# piboard.net
KiCad netlist of a schematic drawn in EAGLE
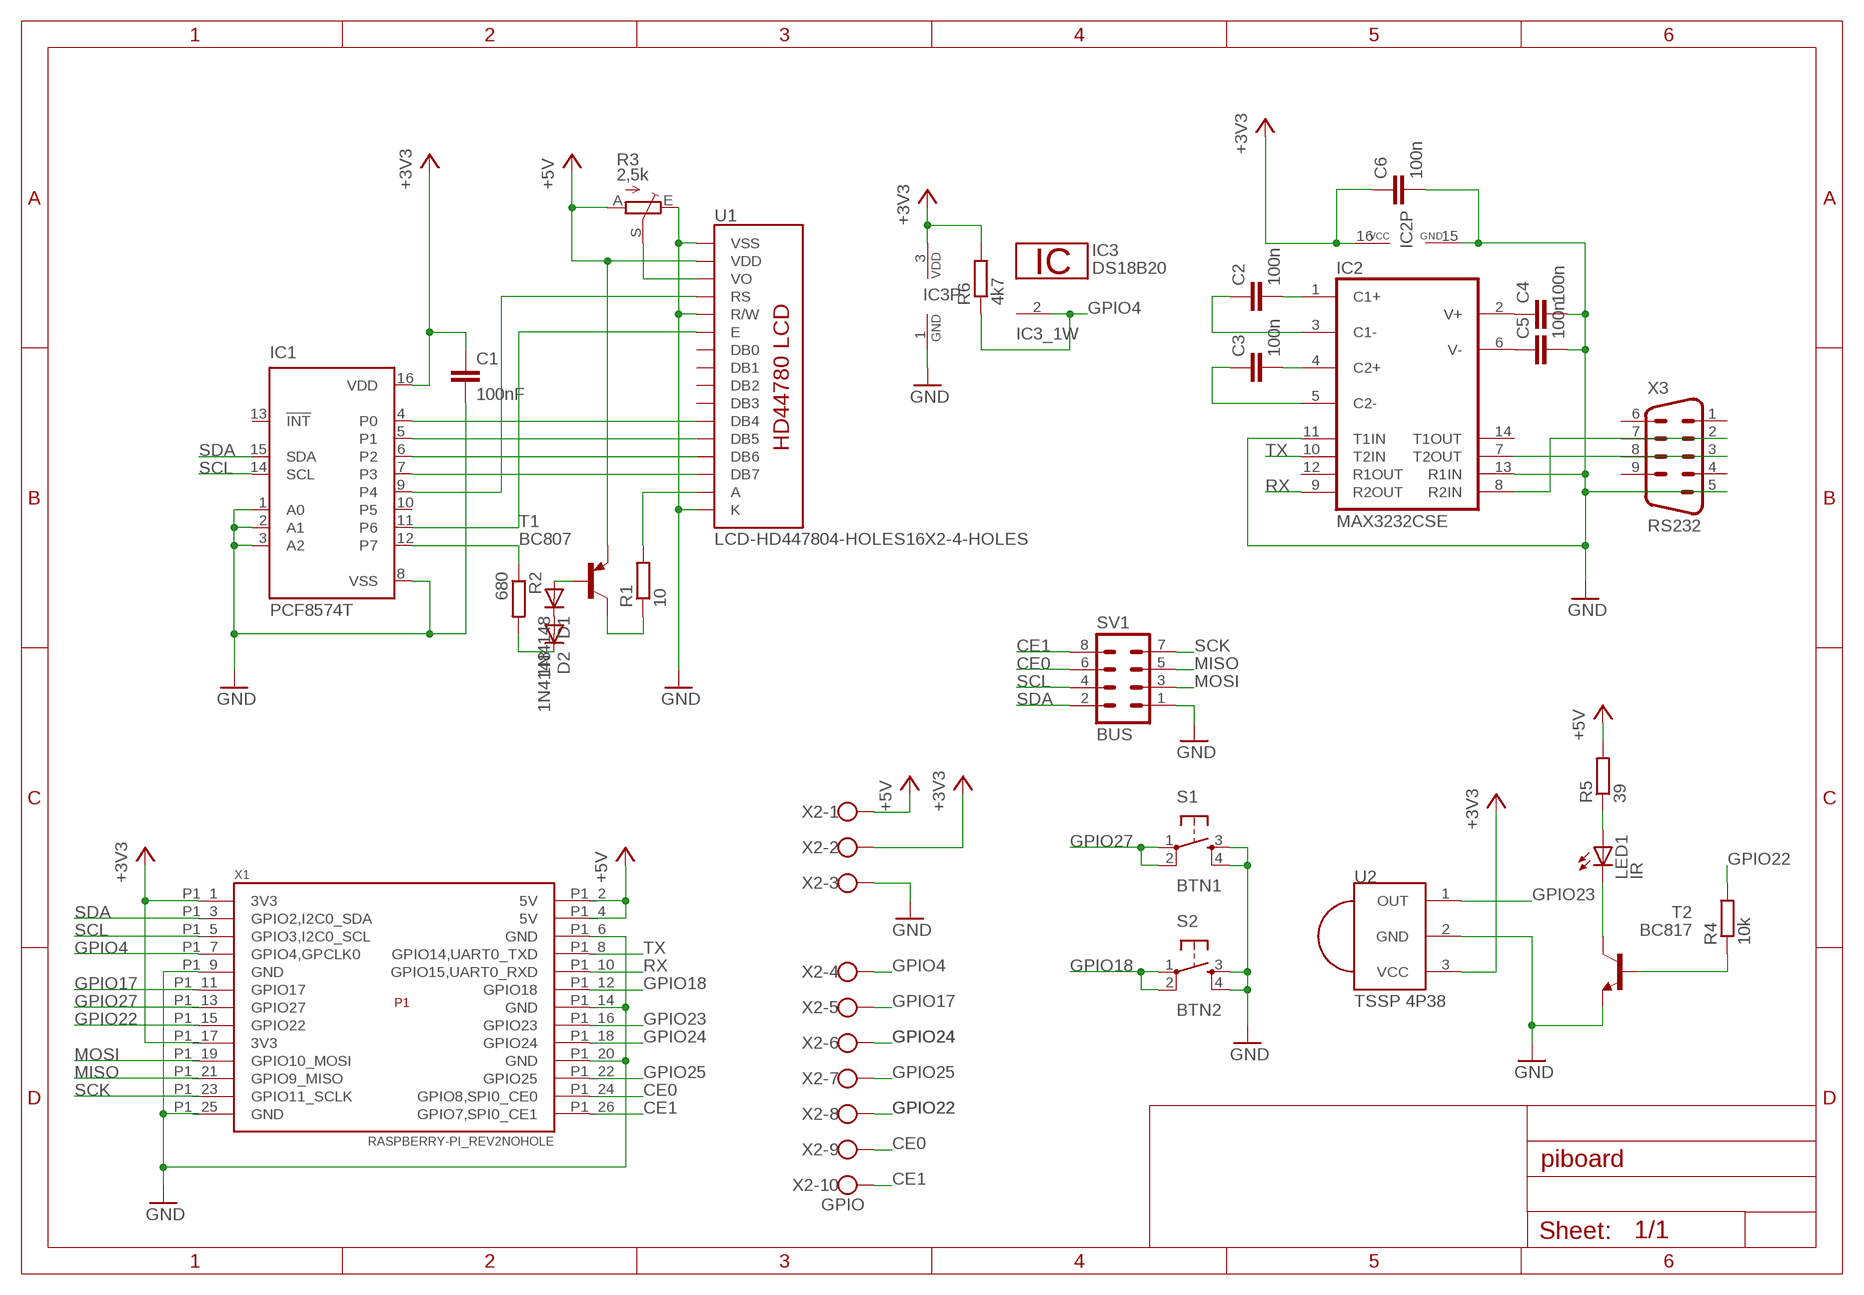
[diagram p0: schematic, sheet 1]

(export (version "E")
  (design (tool "Eeschema 10.0.6"))
  (components
    (comp (ref "C1")
      (value "100nF")
      (footprint "eagle-import:C0805")
      (libsource (lib "eagle-import") (part "C-EUC0805"))
    )
    (comp (ref "C2")
      (value "100n")
      (footprint "eagle-import:C0805")
      (libsource (lib "eagle-import") (part "C-EUC0805"))
    )
    (comp (ref "C3")
      (value "100n")
      (footprint "eagle-import:C0805")
      (libsource (lib "eagle-import") (part "C-EUC0805"))
    )
    (comp (ref "C4")
      (value "100n")
      (footprint "eagle-import:C0805")
      (libsource (lib "eagle-import") (part "C-EUC0805"))
    )
    (comp (ref "C5")
      (value "100n")
      (footprint "eagle-import:C0805")
      (libsource (lib "eagle-import") (part "C-EUC0805"))
    )
    (comp (ref "C6")
      (value "100n")
      (footprint "eagle-import:C0805")
      (libsource (lib "eagle-import") (part "C-EUC0805"))
    )
    (comp (ref "D1")
      (value "1N4148")
      (footprint "eagle-import:SOD80C")
      (libsource (lib "eagle-import") (part "DIODE-SOD80C"))
    )
    (comp (ref "D2")
      (value "1N4148")
      (footprint "eagle-import:SOD80C")
      (libsource (lib "eagle-import") (part "DIODE-SOD80C"))
    )
    (comp (ref "IC1")
      (value "PCF8574T")
      (footprint "eagle-import:SO16W")
      (fields (field (name "MPN") "PCF8574T/3,512"))
      (libsource (lib "eagle-import") (part "PCF8574T"))
    )
    (comp (ref "IC2")
      (value "MAX3232CSE")
      (footprint "eagle-import:SO16")
      (libsource (lib "eagle-import") (part "MAX3232SEC"))
    )
    (comp (ref "IC3")
      (value "DS18B20")
      (footprint "eagle-import:TO92-")
      (libsource (lib "eagle-import") (part "DS18B20"))
    )
    (comp (ref "LED1")
      (value "IR")
      (footprint "eagle-import:LED5MM")
      (libsource (lib "eagle-import") (part "LED5MM"))
    )
    (comp (ref "R1")
      (value "10")
      (footprint "eagle-import:R0805")
      (libsource (lib "eagle-import") (part "R-EU_R0805"))
    )
    (comp (ref "R2")
      (value "680")
      (footprint "eagle-import:R0805")
      (libsource (lib "eagle-import") (part "R-EU_R0805"))
    )
    (comp (ref "R3")
      (value "2,5k")
      (footprint "eagle-import:LI6")
      (libsource (lib "eagle-import") (part "TRIM_EU-2"))
    )
    (comp (ref "R4")
      (value "10k")
      (footprint "eagle-import:R0805")
      (libsource (lib "eagle-import") (part "R-EU_R0805"))
    )
    (comp (ref "R5")
      (value "39")
      (footprint "eagle-import:R0805")
      (libsource (lib "eagle-import") (part "R-EU_R0805"))
    )
    (comp (ref "R6")
      (value "4k7")
      (footprint "eagle-import:R0805")
      (libsource (lib "eagle-import") (part "R-EU_R0805"))
    )
    (comp (ref "S1")
      (value "BTN1")
      (footprint "eagle-import:TACTILE-PTH")
      (libsource (lib "eagle-import") (part "TAC_SWITCHPTH"))
    )
    (comp (ref "S2")
      (value "BTN2")
      (footprint "eagle-import:TACTILE-PTH")
      (libsource (lib "eagle-import") (part "TAC_SWITCHPTH"))
    )
    (comp (ref "SV1")
      (value "BUS")
      (footprint "eagle-import:MA04-2")
      (libsource (lib "eagle-import") (part "MA04-2"))
    )
    (comp (ref "T1")
      (value "BC807")
      (footprint "eagle-import:SOT23-BEC")
      (libsource (lib "eagle-import") (part "-PNP-SOT23-BECBC807-16"))
    )
    (comp (ref "T2")
      (value "BC817")
      (footprint "eagle-import:SOT23-BEC")
      (libsource (lib "eagle-import") (part "-NPN-SOT23-BECBC817-16"))
    )
    (comp (ref "U1")
      (value "LCD-HD447804-HOLES16X2-4-HOLES")
      (footprint "eagle-import:LCD-16X2-4HOLES")
      (libsource (lib "eagle-import") (part "LCD-HD4478016X2-4-HOLES4-HOLES"))
    )
    (comp (ref "U2")
      (value "TSSP 4P38")
      (footprint "eagle-import:PNA460XM")
      (libsource (lib "eagle-import") (part "adafruit-eagle610_PNA460XM"))
    )
    (comp (ref "X1")
      (value "RASPBERRY-PI_REV2NOHOLE")
      (footprint "eagle-import:RASPBERRY-PI_REV2_NOHOLE")
      (libsource (lib "eagle-import") (part "RASPBERRY-PI_REV2NOHOLE"))
    )
    (comp (ref "X2")
      (value "GPIO")
      (footprint "eagle-import:RIA059-10")
      (libsource (lib "eagle-import") (part "AKL059-10"))
    )
    (comp (ref "X3")
      (value "RS232")
      (footprint "eagle-import:M09HP")
      (libsource (lib "eagle-import") (part "M09HP"))
    )
  )
  (nets
    (net (code "1") (name "+3V3") (class "Default")
      (node (ref "C1") (pin "1") (pinfunction "1_1") (pintype "passive"))
      (node (ref "C6") (pin "1") (pinfunction "1_1") (pintype "passive"))
      (node (ref "IC1") (pin "16") (pinfunction "VDD_16") (pintype "power_in"))
      (node (ref "IC2") (pin "16") (pinfunction "VCC_16") (pintype "power_in"))
      (node (ref "IC3") (pin "3") (pinfunction "VDD_3") (pintype "power_in"))
      (node (ref "R6") (pin "2") (pinfunction "2_2") (pintype "passive"))
      (node (ref "U2") (pin "3") (pinfunction "VCC_3") (pintype "power_in"))
      (node (ref "X1") (pin "P1_1") (pinfunction "3V3_P1_1") (pintype "bidirectional"))
      (node (ref "X1") (pin "P1_17") (pinfunction "3V3_P1_17") (pintype "bidirectional"))
      (node (ref "X2") (pin "2") (pinfunction "KL_2") (pintype "passive"))
    )
    (net (code "2") (name "+5V") (class "Default")
      (node (ref "R3") (pin "A") (pinfunction "A_A") (pintype "passive"))
      (node (ref "R5") (pin "2") (pinfunction "2_2") (pintype "passive"))
      (node (ref "T1") (pin "E") (pinfunction "E_E") (pintype "passive"))
      (node (ref "U1") (pin "2") (pinfunction "VDD_2") (pintype "power_in"))
      (node (ref "X1") (pin "P1_2") (pinfunction "5V_P1_2") (pintype "bidirectional"))
      (node (ref "X1") (pin "P1_4") (pinfunction "5V_P1_4") (pintype "bidirectional"))
      (node (ref "X2") (pin "1") (pinfunction "KL_1") (pintype "passive"))
    )
    (net (code "3") (name "/CE0") (class "Default")
      (node (ref "SV1") (pin "6") (pinfunction "6_6") (pintype "passive"))
      (node (ref "X1") (pin "P1_24") (pinfunction "GPIO8,SPI0_CE0_P1_24") (pintype "bidirectional"))
      (node (ref "X2") (pin "9") (pinfunction "KL_9") (pintype "passive"))
    )
    (net (code "4") (name "/CE1") (class "Default")
      (node (ref "SV1") (pin "8") (pinfunction "8_8") (pintype "passive"))
      (node (ref "X1") (pin "P1_26") (pinfunction "GPIO7,SPI0_CE1_P1_26") (pintype "bidirectional"))
      (node (ref "X2") (pin "10") (pinfunction "KL_10") (pintype "passive"))
    )
    (net (code "5") (name "/GPIO4") (class "Default")
      (node (ref "IC3") (pin "2") (pinfunction "1W_2") (pintype "power_in"))
      (node (ref "R6") (pin "1") (pinfunction "1_1") (pintype "passive"))
      (node (ref "X1") (pin "P1_7") (pinfunction "GPIO4,GPCLK0_P1_7") (pintype "bidirectional"))
      (node (ref "X2") (pin "4") (pinfunction "KL_4") (pintype "passive"))
    )
    (net (code "6") (name "/GPIO17") (class "Default")
      (node (ref "X1") (pin "P1_11") (pinfunction "GPIO17_P1_11") (pintype "bidirectional"))
      (node (ref "X2") (pin "5") (pinfunction "KL_5") (pintype "passive"))
    )
    (net (code "7") (name "/GPIO18") (class "Default")
      (node (ref "S2") (pin "1") (pinfunction "1_1") (pintype "passive"))
      (node (ref "S2") (pin "2") (pinfunction "2_2") (pintype "passive"))
      (node (ref "X1") (pin "P1_12") (pinfunction "GPIO18_P1_12") (pintype "bidirectional"))
    )
    (net (code "8") (name "/GPIO22") (class "Default")
      (node (ref "R4") (pin "2") (pinfunction "2_2") (pintype "passive"))
      (node (ref "X1") (pin "P1_15") (pinfunction "GPIO22_P1_15") (pintype "bidirectional"))
      (node (ref "X2") (pin "8") (pinfunction "KL_8") (pintype "passive"))
    )
    (net (code "9") (name "/GPIO23") (class "Default")
      (node (ref "U2") (pin "1") (pinfunction "OUT_1") (pintype "output"))
      (node (ref "X1") (pin "P1_16") (pinfunction "GPIO23_P1_16") (pintype "bidirectional"))
    )
    (net (code "10") (name "/GPIO24") (class "Default")
      (node (ref "X1") (pin "P1_18") (pinfunction "GPIO24_P1_18") (pintype "bidirectional"))
      (node (ref "X2") (pin "6") (pinfunction "KL_6") (pintype "passive"))
    )
    (net (code "11") (name "/GPIO25") (class "Default")
      (node (ref "X1") (pin "P1_22") (pinfunction "GPIO25_P1_22") (pintype "bidirectional"))
      (node (ref "X2") (pin "7") (pinfunction "KL_7") (pintype "passive"))
    )
    (net (code "12") (name "/GPIO27") (class "Default")
      (node (ref "S1") (pin "1") (pinfunction "1_1") (pintype "passive"))
      (node (ref "S1") (pin "2") (pinfunction "2_2") (pintype "passive"))
      (node (ref "X1") (pin "P1_13") (pinfunction "GPIO27_P1_13") (pintype "bidirectional"))
    )
    (net (code "13") (name "/MISO") (class "Default")
      (node (ref "SV1") (pin "5") (pinfunction "5_5") (pintype "passive"))
      (node (ref "X1") (pin "P1_21") (pinfunction "GPIO9_MISO_P1_21") (pintype "bidirectional"))
    )
    (net (code "14") (name "/MOSI") (class "Default")
      (node (ref "SV1") (pin "3") (pinfunction "3_3") (pintype "passive"))
      (node (ref "X1") (pin "P1_19") (pinfunction "GPIO10_MOSI_P1_19") (pintype "bidirectional"))
    )
    (net (code "15") (name "/RX") (class "Default")
      (node (ref "IC2") (pin "9") (pinfunction "R2OUT_9") (pintype "output"))
      (node (ref "X1") (pin "P1_10") (pinfunction "GPIO15,UART0_RXD_P1_10") (pintype "bidirectional"))
    )
    (net (code "16") (name "/SCK") (class "Default")
      (node (ref "SV1") (pin "7") (pinfunction "7_7") (pintype "passive"))
      (node (ref "X1") (pin "P1_23") (pinfunction "GPIO11_SCLK_P1_23") (pintype "bidirectional"))
    )
    (net (code "17") (name "/SCL") (class "Default")
      (node (ref "IC1") (pin "14") (pinfunction "SCL_14") (pintype "input"))
      (node (ref "SV1") (pin "4") (pinfunction "4_4") (pintype "passive"))
      (node (ref "X1") (pin "P1_5") (pinfunction "GPIO3,I2C0_SCL_P1_5") (pintype "bidirectional"))
    )
    (net (code "18") (name "/SDA") (class "Default")
      (node (ref "IC1") (pin "15") (pinfunction "SDA_15") (pintype "bidirectional"))
      (node (ref "SV1") (pin "2") (pinfunction "2_2") (pintype "passive"))
      (node (ref "X1") (pin "P1_3") (pinfunction "GPIO2,I2C0_SDA_P1_3") (pintype "bidirectional"))
    )
    (net (code "19") (name "/TX") (class "Default")
      (node (ref "IC2") (pin "10") (pinfunction "T2IN_10") (pintype "input"))
      (node (ref "X1") (pin "P1_8") (pinfunction "GPIO14,UART0_TXD_P1_8") (pintype "bidirectional"))
    )
    (net (code "20") (name "GND") (class "Default")
      (node (ref "C1") (pin "2") (pinfunction "2_2") (pintype "passive"))
      (node (ref "C4") (pin "2") (pinfunction "2_2") (pintype "passive"))
      (node (ref "C5") (pin "2") (pinfunction "2_2") (pintype "passive"))
      (node (ref "C6") (pin "2") (pinfunction "2_2") (pintype "passive"))
      (node (ref "IC1") (pin "1") (pinfunction "A0_1") (pintype "input"))
      (node (ref "IC1") (pin "2") (pinfunction "A1_2") (pintype "input"))
      (node (ref "IC1") (pin "3") (pinfunction "A2_3") (pintype "input"))
      (node (ref "IC1") (pin "8") (pinfunction "VSS_8") (pintype "power_in"))
      (node (ref "IC2") (pin "11") (pinfunction "T1IN_11") (pintype "input"))
      (node (ref "IC2") (pin "13") (pinfunction "R1IN_13") (pintype "input"))
      (node (ref "IC2") (pin "15") (pinfunction "GND_15") (pintype "power_in"))
      (node (ref "IC3") (pin "1") (pinfunction "GND_1") (pintype "power_in"))
      (node (ref "R3") (pin "E") (pinfunction "E_E") (pintype "passive"))
      (node (ref "S1") (pin "3") (pinfunction "3_3") (pintype "passive"))
      (node (ref "S1") (pin "4") (pinfunction "4_4") (pintype "passive"))
      (node (ref "S2") (pin "3") (pinfunction "3_3") (pintype "passive"))
      (node (ref "S2") (pin "4") (pinfunction "4_4") (pintype "passive"))
      (node (ref "SV1") (pin "1") (pinfunction "1_1") (pintype "passive"))
      (node (ref "T2") (pin "E") (pinfunction "E_E") (pintype "passive"))
      (node (ref "U1") (pin "1") (pinfunction "VSS_1") (pintype "power_in"))
      (node (ref "U1") (pin "16") (pinfunction "K_16") (pintype "passive"))
      (node (ref "U1") (pin "5") (pinfunction "R/W_5") (pintype "input"))
      (node (ref "U2") (pin "2") (pinfunction "GND_2") (pintype "power_in"))
      (node (ref "X1") (pin "P1_14") (pinfunction "GND_P1_14") (pintype "bidirectional"))
      (node (ref "X1") (pin "P1_20") (pinfunction "GND_P1_20") (pintype "bidirectional"))
      (node (ref "X1") (pin "P1_25") (pinfunction "GND_P1_25") (pintype "bidirectional"))
      (node (ref "X1") (pin "P1_6") (pinfunction "GND_P1_6") (pintype "bidirectional"))
      (node (ref "X1") (pin "P1_9") (pinfunction "GND_P1_9") (pintype "bidirectional"))
      (node (ref "X2") (pin "3") (pinfunction "KL_3") (pintype "passive"))
      (node (ref "X3") (pin "5") (pinfunction "5_5") (pintype "passive"))
    )
    (net (code "21") (name "Net-(D1-PadA)") (class "Default")
      (node (ref "D1") (pin "A") (pinfunction "A_A") (pintype "passive"))
      (node (ref "T1") (pin "B") (pinfunction "B_B") (pintype "passive"))
    )
    (net (code "22") (name "Net-(D1-PadC)") (class "Default")
      (node (ref "D1") (pin "C") (pinfunction "C_C") (pintype "passive"))
      (node (ref "D2") (pin "A") (pinfunction "A_A") (pintype "passive"))
    )
    (net (code "23") (name "Net-(D2-PadC)") (class "Default")
      (node (ref "D2") (pin "C") (pinfunction "C_C") (pintype "passive"))
      (node (ref "R2") (pin "2") (pinfunction "2_2") (pintype "passive"))
    )
    (net (code "24") (name "Net-(IC1-P0)") (class "Default")
      (node (ref "IC1") (pin "4") (pinfunction "P0_4") (pintype "bidirectional"))
      (node (ref "U1") (pin "11") (pinfunction "DB4_11") (pintype "bidirectional"))
    )
    (net (code "25") (name "Net-(IC1-P1)") (class "Default")
      (node (ref "IC1") (pin "5") (pinfunction "P1_5") (pintype "bidirectional"))
      (node (ref "U1") (pin "12") (pinfunction "DB5_12") (pintype "bidirectional"))
    )
    (net (code "26") (name "Net-(IC1-P2)") (class "Default")
      (node (ref "IC1") (pin "6") (pinfunction "P2_6") (pintype "bidirectional"))
      (node (ref "U1") (pin "13") (pinfunction "DB6_13") (pintype "bidirectional"))
    )
    (net (code "27") (name "Net-(IC1-P3)") (class "Default")
      (node (ref "IC1") (pin "7") (pinfunction "P3_7") (pintype "bidirectional"))
      (node (ref "U1") (pin "14") (pinfunction "DB7_14") (pintype "bidirectional"))
    )
    (net (code "28") (name "Net-(IC1-P4)") (class "Default")
      (node (ref "IC1") (pin "9") (pinfunction "P4_9") (pintype "bidirectional"))
      (node (ref "U1") (pin "4") (pinfunction "RS_4") (pintype "input"))
    )
    (net (code "29") (name "Net-(IC1-P6)") (class "Default")
      (node (ref "IC1") (pin "11") (pinfunction "P6_11") (pintype "bidirectional"))
      (node (ref "U1") (pin "6") (pinfunction "E_6") (pintype "input"))
    )
    (net (code "30") (name "Net-(IC1-P7)") (class "Default")
      (node (ref "IC1") (pin "12") (pinfunction "P7_12") (pintype "bidirectional"))
      (node (ref "R2") (pin "1") (pinfunction "1_1") (pintype "passive"))
    )
    (net (code "31") (name "Net-(IC2A-C1+)") (class "Default")
      (node (ref "C2") (pin "2") (pinfunction "2_2") (pintype "passive"))
      (node (ref "IC2") (pin "1") (pinfunction "C1+_1") (pintype "bidirectional"))
    )
    (net (code "32") (name "Net-(IC2A-C1-)") (class "Default")
      (node (ref "C2") (pin "1") (pinfunction "1_1") (pintype "passive"))
      (node (ref "IC2") (pin "3") (pinfunction "C1-_3") (pintype "bidirectional"))
    )
    (net (code "33") (name "Net-(IC2A-C2+)") (class "Default")
      (node (ref "C3") (pin "2") (pinfunction "2_2") (pintype "passive"))
      (node (ref "IC2") (pin "4") (pinfunction "C2+_4") (pintype "bidirectional"))
    )
    (net (code "34") (name "Net-(IC2A-C2-)") (class "Default")
      (node (ref "C3") (pin "1") (pinfunction "1_1") (pintype "passive"))
      (node (ref "IC2") (pin "5") (pinfunction "C2-_5") (pintype "bidirectional"))
    )
    (net (code "35") (name "Net-(IC2A-R2IN)") (class "Default")
      (node (ref "IC2") (pin "8") (pinfunction "R2IN_8") (pintype "input"))
      (node (ref "X3") (pin "2") (pinfunction "2_2") (pintype "passive"))
    )
    (net (code "36") (name "Net-(IC2A-T2OUT)") (class "Default")
      (node (ref "IC2") (pin "7") (pinfunction "T2OUT_7") (pintype "output"))
      (node (ref "X3") (pin "3") (pinfunction "3_3") (pintype "passive"))
    )
    (net (code "37") (name "Net-(IC2A-V+)") (class "Default")
      (node (ref "C4") (pin "1") (pinfunction "1_1") (pintype "passive"))
      (node (ref "IC2") (pin "2") (pinfunction "V+_2") (pintype "bidirectional"))
    )
    (net (code "38") (name "Net-(IC2A-V-)") (class "Default")
      (node (ref "C5") (pin "1") (pinfunction "1_1") (pintype "passive"))
      (node (ref "IC2") (pin "6") (pinfunction "V-_6") (pintype "bidirectional"))
    )
    (net (code "39") (name "Net-(LED1-C)") (class "Default")
      (node (ref "LED1") (pin "K") (pinfunction "C_K") (pintype "passive"))
      (node (ref "T2") (pin "C") (pinfunction "C_C") (pintype "passive"))
    )
    (net (code "40") (name "Net-(LED1-PadA)") (class "Default")
      (node (ref "LED1") (pin "A") (pinfunction "A_A") (pintype "passive"))
      (node (ref "R5") (pin "1") (pinfunction "1_1") (pintype "passive"))
    )
    (net (code "41") (name "Net-(R1-Pad1)") (class "Default")
      (node (ref "R1") (pin "1") (pinfunction "1_1") (pintype "passive"))
      (node (ref "T1") (pin "C") (pinfunction "C_C") (pintype "passive"))
    )
    (net (code "42") (name "Net-(R4-Pad1)") (class "Default")
      (node (ref "R4") (pin "1") (pinfunction "1_1") (pintype "passive"))
      (node (ref "T2") (pin "B") (pinfunction "B_B") (pintype "passive"))
    )
    (net (code "43") (name "Net-(U1-A)") (class "Default")
      (node (ref "R1") (pin "2") (pinfunction "2_2") (pintype "passive"))
      (node (ref "U1") (pin "15") (pinfunction "A_15") (pintype "passive"))
    )
    (net (code "44") (name "Net-(U1-VO)") (class "Default")
      (node (ref "R3") (pin "S") (pinfunction "S_S") (pintype "passive"))
      (node (ref "U1") (pin "3") (pinfunction "VO_3") (pintype "bidirectional"))
    )
    (net (code "45") (name "unconnected-(IC1-P5-Pad10)") (class "Default")
      (node (ref "IC1") (pin "10") (pinfunction "P5_10") (pintype "bidirectional"))
    )
    (net (code "46") (name "unconnected-(IC1-~{INT}-Pad13)") (class "Default")
      (node (ref "IC1") (pin "13") (pinfunction "~{INT}_13") (pintype "output"))
    )
    (net (code "47") (name "unconnected-(IC2A-R1OUT-Pad12)") (class "Default")
      (node (ref "IC2") (pin "12") (pinfunction "R1OUT_12") (pintype "output"))
    )
    (net (code "48") (name "unconnected-(IC2A-T1OUT-Pad14)") (class "Default")
      (node (ref "IC2") (pin "14") (pinfunction "T1OUT_14") (pintype "output"))
    )
    (net (code "49") (name "unconnected-(U1-DB0-Pad7)") (class "Default")
      (node (ref "U1") (pin "7") (pinfunction "DB0_7") (pintype "bidirectional"))
    )
    (net (code "50") (name "unconnected-(U1-DB1-Pad8)") (class "Default")
      (node (ref "U1") (pin "8") (pinfunction "DB1_8") (pintype "bidirectional"))
    )
    (net (code "51") (name "unconnected-(U1-DB2-Pad9)") (class "Default")
      (node (ref "U1") (pin "9") (pinfunction "DB2_9") (pintype "bidirectional"))
    )
    (net (code "52") (name "unconnected-(U1-DB3-Pad10)") (class "Default")
      (node (ref "U1") (pin "10") (pinfunction "DB3_10") (pintype "bidirectional"))
    )
    (net (code "53") (name "unconnected-(X3-Pad1)") (class "Default")
      (node (ref "X3") (pin "1") (pinfunction "1_1") (pintype "passive"))
    )
    (net (code "54") (name "unconnected-(X3-Pad4)") (class "Default")
      (node (ref "X3") (pin "4") (pinfunction "4_4") (pintype "passive"))
    )
    (net (code "55") (name "unconnected-(X3-Pad6)") (class "Default")
      (node (ref "X3") (pin "6") (pinfunction "6_6") (pintype "passive"))
    )
    (net (code "56") (name "unconnected-(X3-Pad7)") (class "Default")
      (node (ref "X3") (pin "7") (pinfunction "7_7") (pintype "passive"))
    )
    (net (code "57") (name "unconnected-(X3-Pad8)") (class "Default")
      (node (ref "X3") (pin "8") (pinfunction "8_8") (pintype "passive"))
    )
    (net (code "58") (name "unconnected-(X3-Pad9)") (class "Default")
      (node (ref "X3") (pin "9") (pinfunction "9_9") (pintype "passive"))
    )
  )
)
